# DAWA-SWITCH-6_3.net
KiCad netlist of a schematic drawn in EAGLE
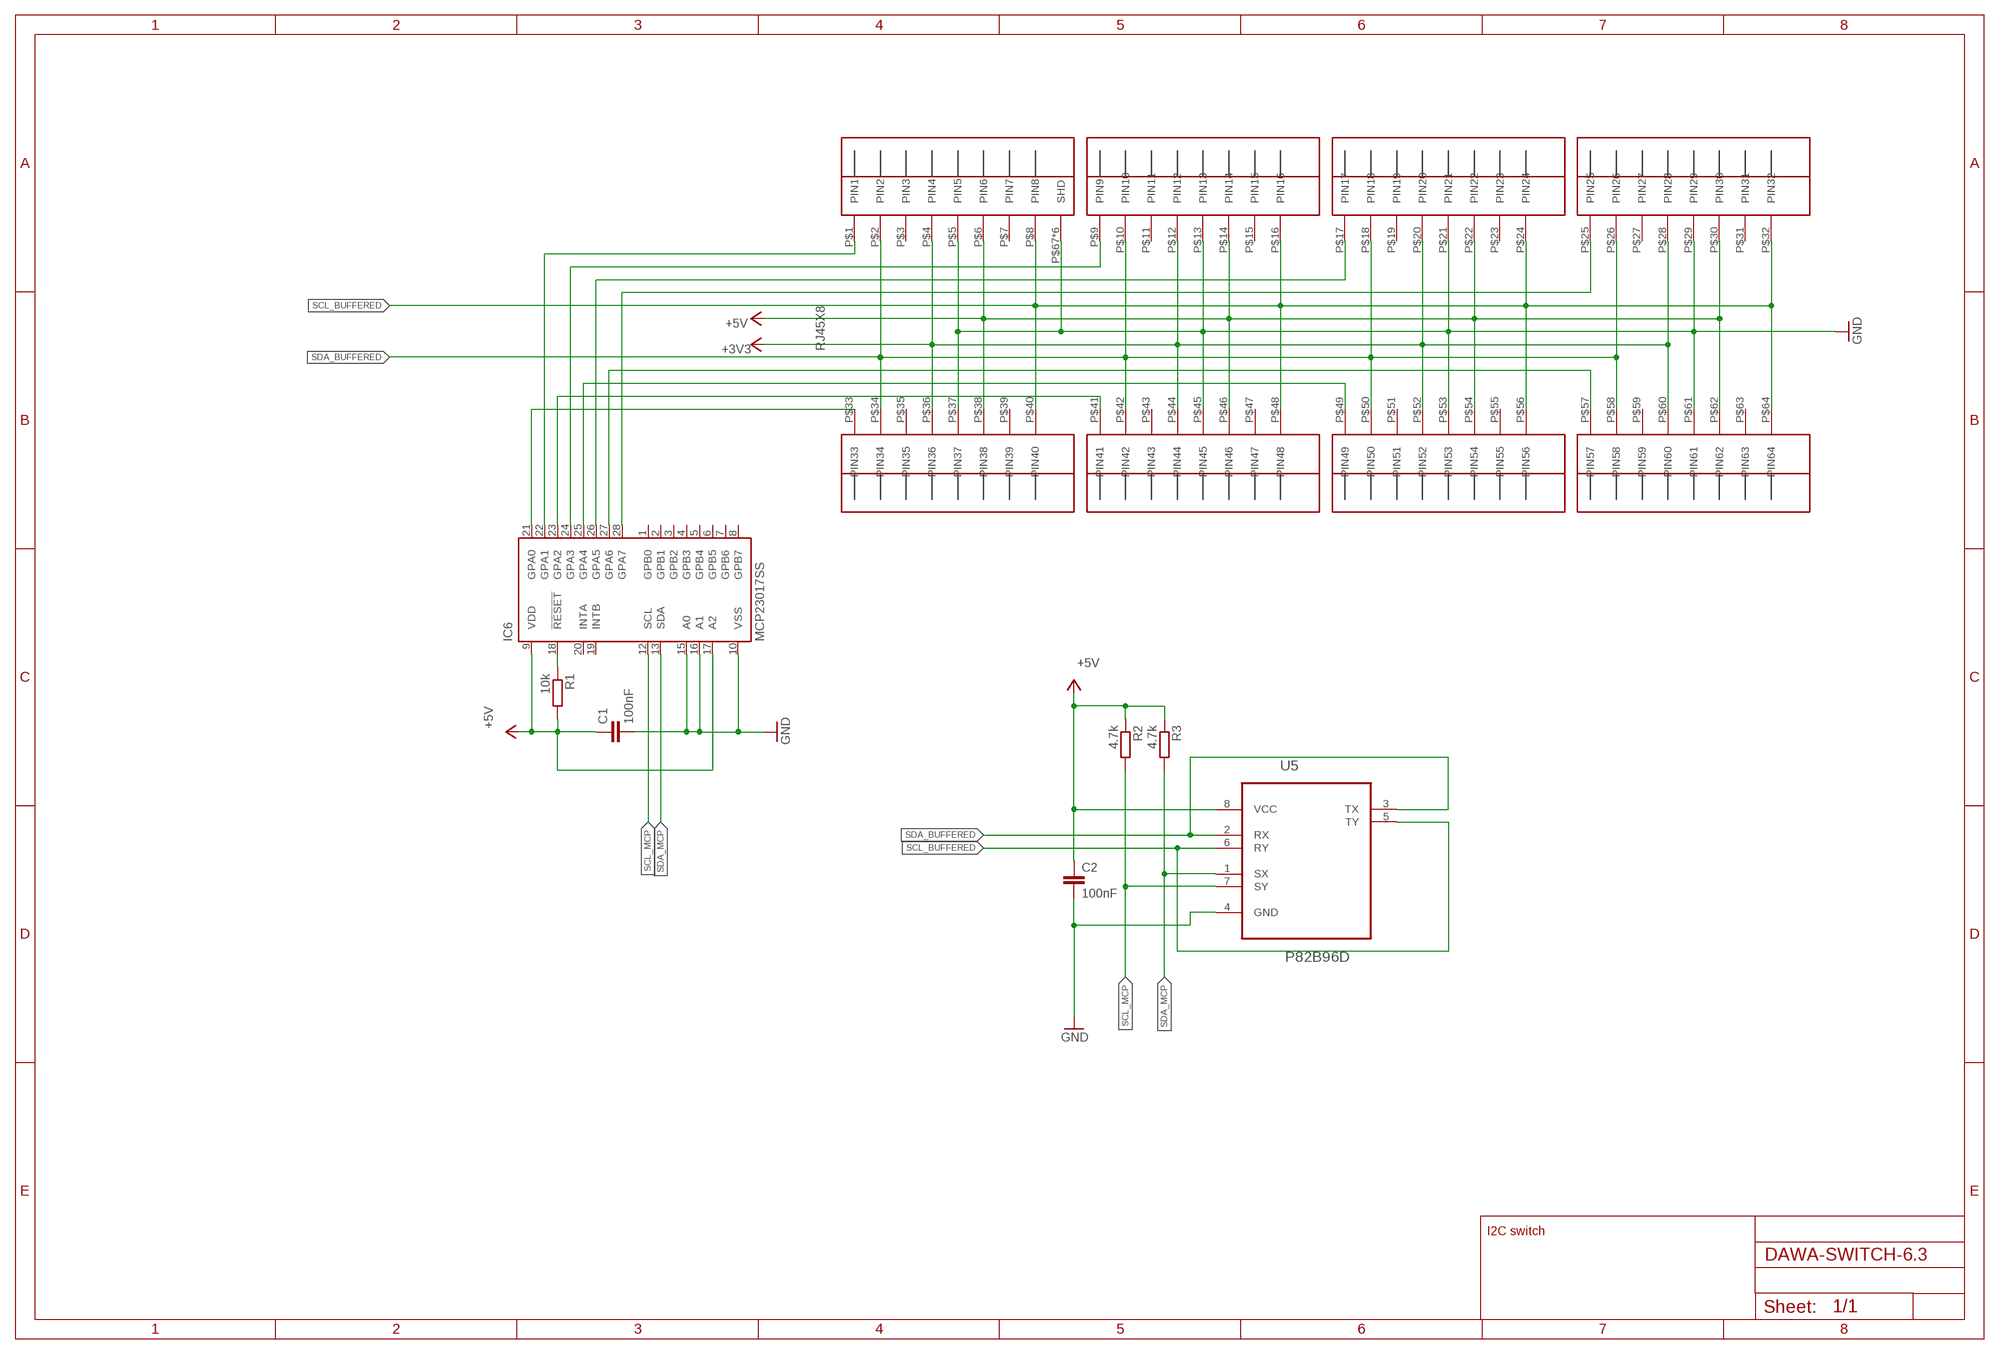
[diagram p0: schematic, sheet 1]

(export (version "E")
  (design (tool "Eeschema 10.0.6"))
  (components
    (comp (ref "C1")
      (value "100nF")
      (footprint "eagle-import:C0603")
      (libsource (lib "eagle-import") (part "rcl_334_C-EUC0603"))
    )
    (comp (ref "C2")
      (value "100nF")
      (footprint "eagle-import:C0603")
      (libsource (lib "eagle-import") (part "C-EUC0603"))
    )
    (comp (ref "IC6")
      (value "MCP23017SS")
      (footprint "eagle-import:SSOP28")
      (libsource (lib "eagle-import") (part "MCP23017SS"))
    )
    (comp (ref "R1")
      (value "10k")
      (footprint "eagle-import:R0603")
      (libsource (lib "eagle-import") (part "R-EU_R0603"))
    )
    (comp (ref "R2")
      (value "4.7k")
      (footprint "eagle-import:R0603")
      (libsource (lib "eagle-import") (part "resistor_R-EU_R0603"))
    )
    (comp (ref "R3")
      (value "4.7k")
      (footprint "eagle-import:R0603")
      (libsource (lib "eagle-import") (part "resistor_R-EU_R0603"))
    )
    (comp (ref "U$18")
      (value "RJ45X8")
      (footprint "eagle-import:RJ45X8")
      (libsource (lib "eagle-import") (part "RJ45X8"))
    )
    (comp (ref "U5")
      (value "P82B96D")
      (footprint "eagle-import:SOIC127P600X175-8N")
      (libsource (lib "eagle-import") (part "P82B96D"))
    )
  )
  (nets
    (net (code "1") (name "+3V3") (class "Default")
      (node (ref "U$18") (pin "P$12") (pinfunction "PIN12_P$12") (pintype "bidirectional"))
      (node (ref "U$18") (pin "P$20") (pinfunction "PIN20_P$20") (pintype "bidirectional"))
      (node (ref "U$18") (pin "P$28") (pinfunction "PIN28_P$28") (pintype "bidirectional"))
      (node (ref "U$18") (pin "P$36") (pinfunction "PIN36_P$36") (pintype "bidirectional"))
      (node (ref "U$18") (pin "P$4") (pinfunction "PIN4_P$4") (pintype "bidirectional"))
      (node (ref "U$18") (pin "P$44") (pinfunction "PIN44_P$44") (pintype "bidirectional"))
      (node (ref "U$18") (pin "P$52") (pinfunction "PIN52_P$52") (pintype "bidirectional"))
      (node (ref "U$18") (pin "P$60") (pinfunction "PIN60_P$60") (pintype "bidirectional"))
    )
    (net (code "2") (name "+5V") (class "Default")
      (node (ref "C1") (pin "1") (pinfunction "1_1") (pintype "passive"))
      (node (ref "C2") (pin "1") (pinfunction "1_1") (pintype "passive"))
      (node (ref "IC6") (pin "17") (pinfunction "A2_17") (pintype "input"))
      (node (ref "IC6") (pin "9") (pinfunction "VDD_9") (pintype "power_in"))
      (node (ref "R1") (pin "2") (pinfunction "2_2") (pintype "passive"))
      (node (ref "R2") (pin "1") (pinfunction "1_1") (pintype "passive"))
      (node (ref "R3") (pin "1") (pinfunction "1_1") (pintype "passive"))
      (node (ref "U$18") (pin "P$14") (pinfunction "PIN14_P$14") (pintype "bidirectional"))
      (node (ref "U$18") (pin "P$22") (pinfunction "PIN22_P$22") (pintype "bidirectional"))
      (node (ref "U$18") (pin "P$30") (pinfunction "PIN30_P$30") (pintype "bidirectional"))
      (node (ref "U$18") (pin "P$38") (pinfunction "PIN38_P$38") (pintype "bidirectional"))
      (node (ref "U$18") (pin "P$46") (pinfunction "PIN46_P$46") (pintype "bidirectional"))
      (node (ref "U$18") (pin "P$54") (pinfunction "PIN54_P$54") (pintype "bidirectional"))
      (node (ref "U$18") (pin "P$6") (pinfunction "PIN6_P$6") (pintype "bidirectional"))
      (node (ref "U$18") (pin "P$62") (pinfunction "PIN62_P$62") (pintype "bidirectional"))
      (node (ref "U5") (pin "8") (pinfunction "VCC_8") (pintype "power_in"))
    )
    (net (code "3") (name "GND") (class "Default")
      (node (ref "C1") (pin "2") (pinfunction "2_2") (pintype "passive"))
      (node (ref "C2") (pin "2") (pinfunction "2_2") (pintype "passive"))
      (node (ref "IC6") (pin "10") (pinfunction "VSS_10") (pintype "power_in"))
      (node (ref "IC6") (pin "15") (pinfunction "A0_15") (pintype "input"))
      (node (ref "IC6") (pin "16") (pinfunction "A1_16") (pintype "input"))
      (node (ref "U$18") (pin "P$13") (pinfunction "PIN13_P$13") (pintype "bidirectional"))
      (node (ref "U$18") (pin "P$21") (pinfunction "PIN21_P$21") (pintype "bidirectional"))
      (node (ref "U$18") (pin "P$29") (pinfunction "PIN29_P$29") (pintype "bidirectional"))
      (node (ref "U$18") (pin "P$37") (pinfunction "PIN37_P$37") (pintype "bidirectional"))
      (node (ref "U$18") (pin "P$45") (pinfunction "PIN45_P$45") (pintype "bidirectional"))
      (node (ref "U$18") (pin "P$5") (pinfunction "PIN5_P$5") (pintype "bidirectional"))
      (node (ref "U$18") (pin "P$53") (pinfunction "PIN53_P$53") (pintype "bidirectional"))
      (node (ref "U$18") (pin "P$61") (pinfunction "PIN61_P$61") (pintype "bidirectional"))
      (node (ref "U$18") (pin "P$67") (pinfunction "SHD_P$67") (pintype "bidirectional"))
      (node (ref "U$18") (pin "P$68") (pinfunction "SHD_P$68") (pintype "bidirectional"))
      (node (ref "U$18") (pin "P$69") (pinfunction "SHD_P$69") (pintype "bidirectional"))
      (node (ref "U$18") (pin "P$70") (pinfunction "SHD_P$70") (pintype "bidirectional"))
      (node (ref "U$18") (pin "P$71") (pinfunction "SHD_P$71") (pintype "bidirectional"))
      (node (ref "U$18") (pin "P$72") (pinfunction "SHD_P$72") (pintype "bidirectional"))
      (node (ref "U5") (pin "4") (pinfunction "GND_4") (pintype "passive"))
    )
    (net (code "4") (name "Net-(IC6-GPA0)") (class "Default")
      (node (ref "IC6") (pin "21") (pinfunction "GPA0_21") (pintype "bidirectional"))
      (node (ref "U$18") (pin "P$33") (pinfunction "PIN33_P$33") (pintype "bidirectional"))
    )
    (net (code "5") (name "Net-(IC6-GPA1)") (class "Default")
      (node (ref "IC6") (pin "22") (pinfunction "GPA1_22") (pintype "bidirectional"))
      (node (ref "U$18") (pin "P$1") (pinfunction "PIN1_P$1") (pintype "bidirectional"))
    )
    (net (code "6") (name "Net-(IC6-GPA2)") (class "Default")
      (node (ref "IC6") (pin "23") (pinfunction "GPA2_23") (pintype "bidirectional"))
      (node (ref "U$18") (pin "P$41") (pinfunction "PIN41_P$41") (pintype "bidirectional"))
    )
    (net (code "7") (name "Net-(IC6-GPA3)") (class "Default")
      (node (ref "IC6") (pin "24") (pinfunction "GPA3_24") (pintype "bidirectional"))
      (node (ref "U$18") (pin "P$9") (pinfunction "PIN9_P$9") (pintype "bidirectional"))
    )
    (net (code "8") (name "Net-(IC6-GPA4)") (class "Default")
      (node (ref "IC6") (pin "25") (pinfunction "GPA4_25") (pintype "bidirectional"))
      (node (ref "U$18") (pin "P$49") (pinfunction "PIN49_P$49") (pintype "bidirectional"))
    )
    (net (code "9") (name "Net-(IC6-GPA5)") (class "Default")
      (node (ref "IC6") (pin "26") (pinfunction "GPA5_26") (pintype "bidirectional"))
      (node (ref "U$18") (pin "P$17") (pinfunction "PIN17_P$17") (pintype "bidirectional"))
    )
    (net (code "10") (name "Net-(IC6-GPA6)") (class "Default")
      (node (ref "IC6") (pin "27") (pinfunction "GPA6_27") (pintype "bidirectional"))
      (node (ref "U$18") (pin "P$57") (pinfunction "PIN57_P$57") (pintype "bidirectional"))
    )
    (net (code "11") (name "Net-(IC6-GPA7)") (class "Default")
      (node (ref "IC6") (pin "28") (pinfunction "GPA7_28") (pintype "bidirectional"))
      (node (ref "U$18") (pin "P$25") (pinfunction "PIN25_P$25") (pintype "bidirectional"))
    )
    (net (code "12") (name "Net-(IC6-~{RESET})") (class "Default")
      (node (ref "IC6") (pin "18") (pinfunction "~{RESET}_18") (pintype "input"))
      (node (ref "R1") (pin "1") (pinfunction "1_1") (pintype "passive"))
    )
    (net (code "13") (name "SCL_BUFFERED") (class "Default")
      (node (ref "U$18") (pin "P$16") (pinfunction "PIN16_P$16") (pintype "bidirectional"))
      (node (ref "U$18") (pin "P$24") (pinfunction "PIN24_P$24") (pintype "bidirectional"))
      (node (ref "U$18") (pin "P$32") (pinfunction "PIN32_P$32") (pintype "bidirectional"))
      (node (ref "U$18") (pin "P$40") (pinfunction "PIN40_P$40") (pintype "bidirectional"))
      (node (ref "U$18") (pin "P$48") (pinfunction "PIN48_P$48") (pintype "bidirectional"))
      (node (ref "U$18") (pin "P$56") (pinfunction "PIN56_P$56") (pintype "bidirectional"))
      (node (ref "U$18") (pin "P$64") (pinfunction "PIN64_P$64") (pintype "bidirectional"))
      (node (ref "U$18") (pin "P$8") (pinfunction "PIN8_P$8") (pintype "bidirectional"))
      (node (ref "U5") (pin "5") (pinfunction "TY_5") (pintype "output"))
      (node (ref "U5") (pin "6") (pinfunction "RY_6") (pintype "input"))
    )
    (net (code "14") (name "SCL_MCP") (class "Default")
      (node (ref "IC6") (pin "12") (pinfunction "SCL_12") (pintype "input"))
      (node (ref "R2") (pin "2") (pinfunction "2_2") (pintype "passive"))
      (node (ref "U5") (pin "7") (pinfunction "SY_7") (pintype "input"))
    )
    (net (code "15") (name "SDA_BUFFERED") (class "Default")
      (node (ref "U$18") (pin "P$10") (pinfunction "PIN10_P$10") (pintype "bidirectional"))
      (node (ref "U$18") (pin "P$18") (pinfunction "PIN18_P$18") (pintype "bidirectional"))
      (node (ref "U$18") (pin "P$2") (pinfunction "PIN2_P$2") (pintype "bidirectional"))
      (node (ref "U$18") (pin "P$26") (pinfunction "PIN26_P$26") (pintype "bidirectional"))
      (node (ref "U$18") (pin "P$34") (pinfunction "PIN34_P$34") (pintype "bidirectional"))
      (node (ref "U$18") (pin "P$42") (pinfunction "PIN42_P$42") (pintype "bidirectional"))
      (node (ref "U$18") (pin "P$50") (pinfunction "PIN50_P$50") (pintype "bidirectional"))
      (node (ref "U$18") (pin "P$58") (pinfunction "PIN58_P$58") (pintype "bidirectional"))
      (node (ref "U5") (pin "2") (pinfunction "RX_2") (pintype "input"))
      (node (ref "U5") (pin "3") (pinfunction "TX_3") (pintype "output"))
    )
    (net (code "16") (name "SDA_MCP") (class "Default")
      (node (ref "IC6") (pin "13") (pinfunction "SDA_13") (pintype "bidirectional"))
      (node (ref "R3") (pin "2") (pinfunction "2_2") (pintype "passive"))
      (node (ref "U5") (pin "1") (pinfunction "SX_1") (pintype "input"))
    )
    (net (code "17") (name "unconnected-(IC6-GPB0-Pad1)") (class "Default")
      (node (ref "IC6") (pin "1") (pinfunction "GPB0_1") (pintype "bidirectional"))
    )
    (net (code "18") (name "unconnected-(IC6-GPB1-Pad2)") (class "Default")
      (node (ref "IC6") (pin "2") (pinfunction "GPB1_2") (pintype "bidirectional"))
    )
    (net (code "19") (name "unconnected-(IC6-GPB2-Pad3)") (class "Default")
      (node (ref "IC6") (pin "3") (pinfunction "GPB2_3") (pintype "bidirectional"))
    )
    (net (code "20") (name "unconnected-(IC6-GPB3-Pad4)") (class "Default")
      (node (ref "IC6") (pin "4") (pinfunction "GPB3_4") (pintype "bidirectional"))
    )
    (net (code "21") (name "unconnected-(IC6-GPB4-Pad5)") (class "Default")
      (node (ref "IC6") (pin "5") (pinfunction "GPB4_5") (pintype "bidirectional"))
    )
    (net (code "22") (name "unconnected-(IC6-GPB5-Pad6)") (class "Default")
      (node (ref "IC6") (pin "6") (pinfunction "GPB5_6") (pintype "bidirectional"))
    )
    (net (code "23") (name "unconnected-(IC6-GPB6-Pad7)") (class "Default")
      (node (ref "IC6") (pin "7") (pinfunction "GPB6_7") (pintype "bidirectional"))
    )
    (net (code "24") (name "unconnected-(IC6-GPB7-Pad8)") (class "Default")
      (node (ref "IC6") (pin "8") (pinfunction "GPB7_8") (pintype "bidirectional"))
    )
    (net (code "25") (name "unconnected-(IC6-INTA-Pad20)") (class "Default")
      (node (ref "IC6") (pin "20") (pinfunction "INTA_20") (pintype "output"))
    )
    (net (code "26") (name "unconnected-(IC6-INTB-Pad19)") (class "Default")
      (node (ref "IC6") (pin "19") (pinfunction "INTB_19") (pintype "output"))
    )
    (net (code "27") (name "unconnected-(U$18-PIN3-PadP$3)") (class "Default")
      (node (ref "U$18") (pin "P$3") (pinfunction "PIN3_P$3") (pintype "bidirectional"))
    )
    (net (code "28") (name "unconnected-(U$18-PIN7-PadP$7)") (class "Default")
      (node (ref "U$18") (pin "P$7") (pinfunction "PIN7_P$7") (pintype "bidirectional"))
    )
    (net (code "29") (name "unconnected-(U$18-PIN11-PadP$11)") (class "Default")
      (node (ref "U$18") (pin "P$11") (pinfunction "PIN11_P$11") (pintype "bidirectional"))
    )
    (net (code "30") (name "unconnected-(U$18-PIN15-PadP$15)") (class "Default")
      (node (ref "U$18") (pin "P$15") (pinfunction "PIN15_P$15") (pintype "bidirectional"))
    )
    (net (code "31") (name "unconnected-(U$18-PIN19-PadP$19)") (class "Default")
      (node (ref "U$18") (pin "P$19") (pinfunction "PIN19_P$19") (pintype "bidirectional"))
    )
    (net (code "32") (name "unconnected-(U$18-PIN23-PadP$23)") (class "Default")
      (node (ref "U$18") (pin "P$23") (pinfunction "PIN23_P$23") (pintype "bidirectional"))
    )
    (net (code "33") (name "unconnected-(U$18-PIN27-PadP$27)") (class "Default")
      (node (ref "U$18") (pin "P$27") (pinfunction "PIN27_P$27") (pintype "bidirectional"))
    )
    (net (code "34") (name "unconnected-(U$18-PIN31-PadP$31)") (class "Default")
      (node (ref "U$18") (pin "P$31") (pinfunction "PIN31_P$31") (pintype "bidirectional"))
    )
    (net (code "35") (name "unconnected-(U$18-PIN35-PadP$35)") (class "Default")
      (node (ref "U$18") (pin "P$35") (pinfunction "PIN35_P$35") (pintype "bidirectional"))
    )
    (net (code "36") (name "unconnected-(U$18-PIN39-PadP$39)") (class "Default")
      (node (ref "U$18") (pin "P$39") (pinfunction "PIN39_P$39") (pintype "bidirectional"))
    )
    (net (code "37") (name "unconnected-(U$18-PIN43-PadP$43)") (class "Default")
      (node (ref "U$18") (pin "P$43") (pinfunction "PIN43_P$43") (pintype "bidirectional"))
    )
    (net (code "38") (name "unconnected-(U$18-PIN47-PadP$47)") (class "Default")
      (node (ref "U$18") (pin "P$47") (pinfunction "PIN47_P$47") (pintype "bidirectional"))
    )
    (net (code "39") (name "unconnected-(U$18-PIN51-PadP$51)") (class "Default")
      (node (ref "U$18") (pin "P$51") (pinfunction "PIN51_P$51") (pintype "bidirectional"))
    )
    (net (code "40") (name "unconnected-(U$18-PIN55-PadP$55)") (class "Default")
      (node (ref "U$18") (pin "P$55") (pinfunction "PIN55_P$55") (pintype "bidirectional"))
    )
    (net (code "41") (name "unconnected-(U$18-PIN59-PadP$59)") (class "Default")
      (node (ref "U$18") (pin "P$59") (pinfunction "PIN59_P$59") (pintype "bidirectional"))
    )
    (net (code "42") (name "unconnected-(U$18-PIN63-PadP$63)") (class "Default")
      (node (ref "U$18") (pin "P$63") (pinfunction "PIN63_P$63") (pintype "bidirectional"))
    )
  )
)
